# Left_Ref_Sensor_SchDoc.net
KiCad netlist of a schematic drawn in Altium Designer
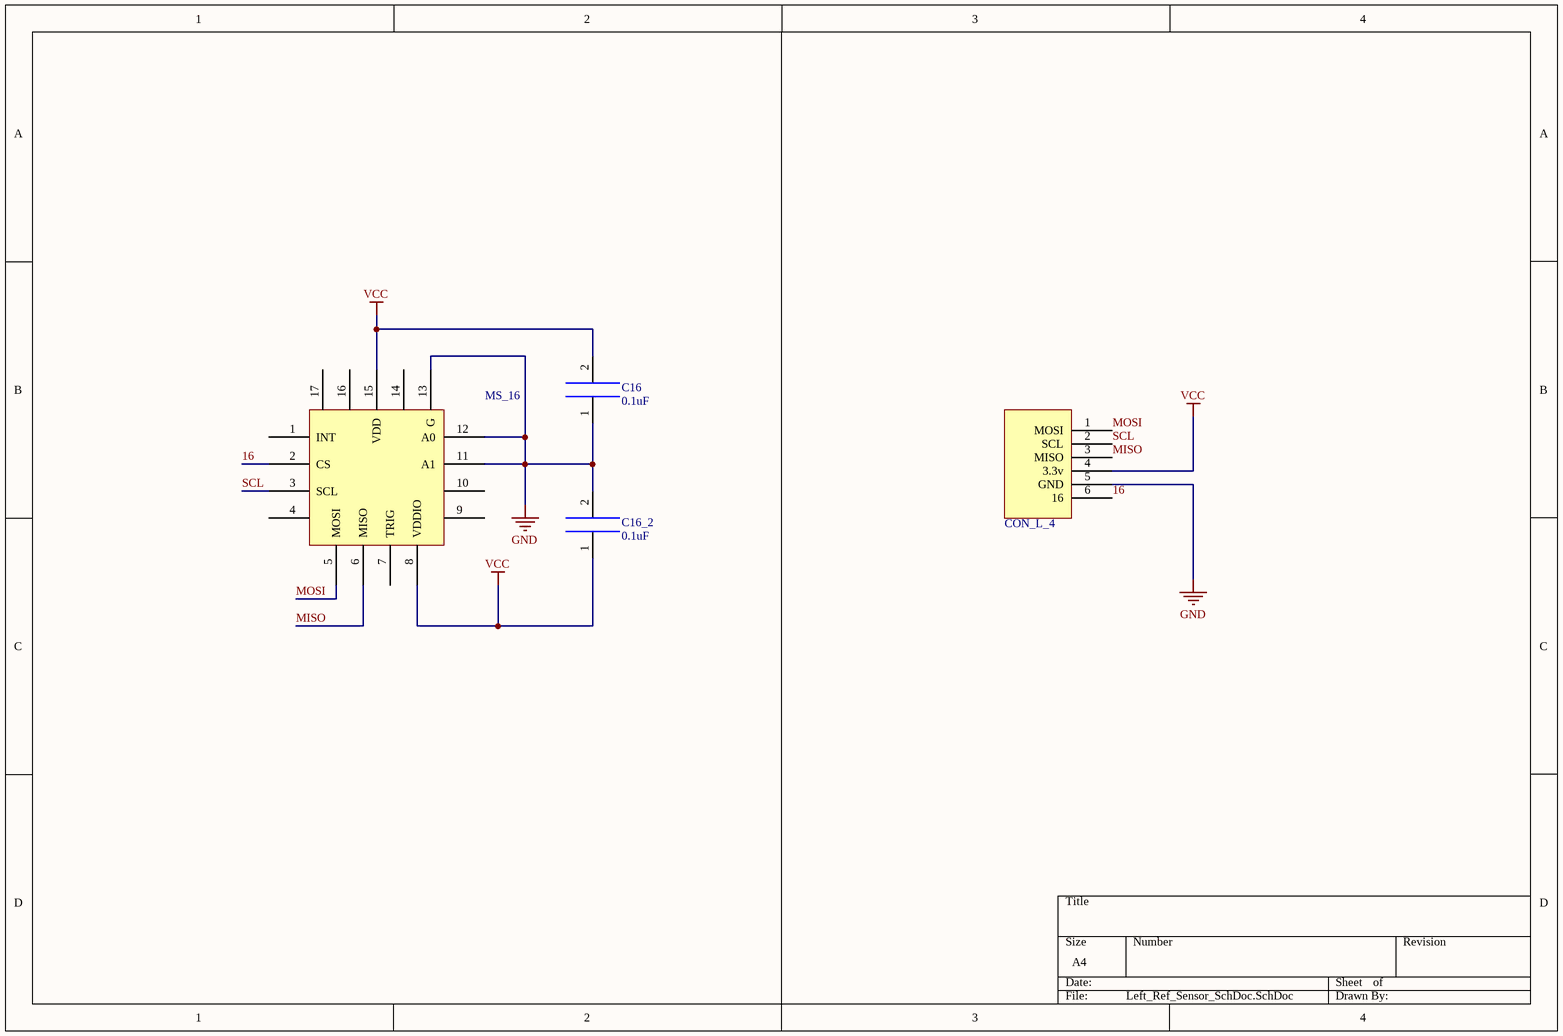
[diagram p0: Left_Ref_Sensor_SchDoc.SchDoc]

(export (version "E")
  (design (tool "Eeschema 10.0.6"))
  (components
    (comp (ref "C16")
      (value "0.1uF")
      (footprint "CAP_0603")
      (description "Capacitance")
      (libsource (lib "MagWaySchlib") (part "CAP"))
    )
    (comp (ref "C16_2")
      (value "0.1uF")
      (footprint "CAP_0603")
      (description "Capacitance")
      (libsource (lib "MagWaySchlib") (part "CAP"))
    )
    (comp (ref "CON_L_4")
      (value "PIN_left")
      (footprint "PIN_Left_4")
      (libsource (lib "MagWaySchlib") (part "PIN_left_4"))
    )
    (comp (ref "MS_16")
      (value "MLX90393SLW ABA 011 RE")
      (footprint "MLX90393")
      (description "MLX90393 Sensor")
      (libsource (lib "MagWaySchlib") (part "MLX90393SLW ABA 011 RE"))
    )
  )
  (nets
    (net (code "1") (name "/16") (class "Default")
      (node (ref "CON_L_4") (pin "6") (pinfunction "16_6") (pintype "passive"))
      (node (ref "MS_16") (pin "2") (pinfunction "CS_2") (pintype "passive"))
    )
    (net (code "2") (name "/MISO") (class "Default")
      (node (ref "CON_L_4") (pin "3") (pinfunction "MISO_3") (pintype "passive"))
      (node (ref "MS_16") (pin "6") (pinfunction "MISO_6") (pintype "passive"))
    )
    (net (code "3") (name "/MOSI") (class "Default")
      (node (ref "CON_L_4") (pin "1") (pinfunction "MOSI_1") (pintype "passive"))
      (node (ref "MS_16") (pin "5") (pinfunction "MOSI_5") (pintype "passive"))
    )
    (net (code "4") (name "/SCL") (class "Default")
      (node (ref "CON_L_4") (pin "2") (pinfunction "SCL_2") (pintype "passive"))
      (node (ref "MS_16") (pin "3") (pinfunction "SCL_3") (pintype "passive"))
    )
    (net (code "5") (name "GND") (class "Default")
      (node (ref "C16") (pin "1") (pintype "passive"))
      (node (ref "C16_2") (pin "2") (pintype "passive"))
      (node (ref "CON_L_4") (pin "5") (pinfunction "GND_5") (pintype "passive"))
      (node (ref "MS_16") (pin "11") (pinfunction "A1_11") (pintype "passive"))
      (node (ref "MS_16") (pin "12") (pinfunction "A0_12") (pintype "passive"))
      (node (ref "MS_16") (pin "13") (pinfunction "G_13") (pintype "passive"))
    )
    (net (code "6") (name "VCC") (class "Default")
      (node (ref "C16") (pin "2") (pintype "passive"))
      (node (ref "C16_2") (pin "1") (pintype "passive"))
      (node (ref "CON_L_4") (pin "4") (pinfunction "3.3v_4") (pintype "passive"))
      (node (ref "MS_16") (pin "15") (pinfunction "VDD_15") (pintype "passive"))
      (node (ref "MS_16") (pin "8") (pinfunction "VDDIO_8") (pintype "passive"))
    )
    (net (code "7") (name "unconnected-(MS_16-INT-Pad1)") (class "Default")
      (node (ref "MS_16") (pin "1") (pinfunction "INT_1") (pintype "passive"))
    )
    (net (code "8") (name "unconnected-(MS_16-Pad4)") (class "Default")
      (node (ref "MS_16") (pin "4") (pintype "passive"))
    )
    (net (code "9") (name "unconnected-(MS_16-Pad9)") (class "Default")
      (node (ref "MS_16") (pin "9") (pintype "passive"))
    )
    (net (code "10") (name "unconnected-(MS_16-Pad10)") (class "Default")
      (node (ref "MS_16") (pin "10") (pintype "passive"))
    )
    (net (code "11") (name "unconnected-(MS_16-Pad14)") (class "Default")
      (node (ref "MS_16") (pin "14") (pintype "passive"))
    )
    (net (code "12") (name "unconnected-(MS_16-Pad16)") (class "Default")
      (node (ref "MS_16") (pin "16") (pintype "passive"))
    )
    (net (code "13") (name "unconnected-(MS_16-Pad17)") (class "Default")
      (node (ref "MS_16") (pin "17") (pintype "passive"))
    )
    (net (code "14") (name "unconnected-(MS_16-TRIG-Pad7)") (class "Default")
      (node (ref "MS_16") (pin "7") (pinfunction "TRIG_7") (pintype "passive"))
    )
  )
)
